# Power.net
KiCad netlist of a schematic drawn in Altium Designer
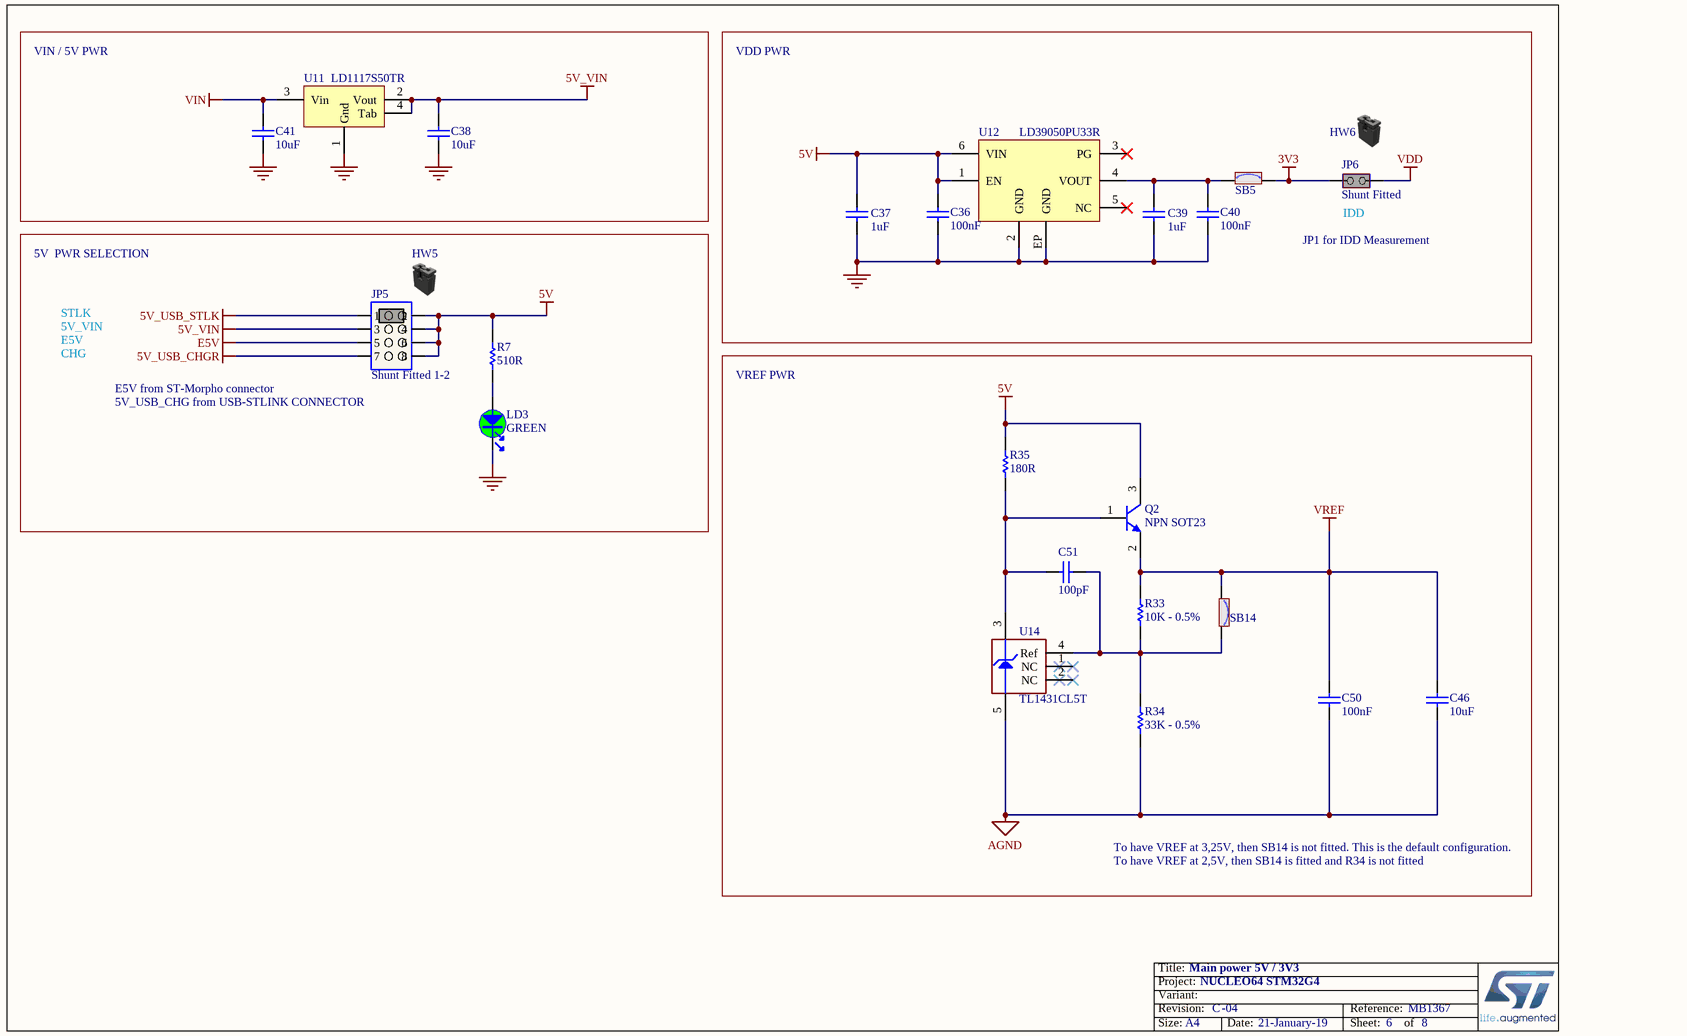
[diagram p0: Power.SchDoc]

(export (version "E")
  (design (tool "Eeschema 10.0.6"))
  (components
    (comp (ref "C36")
      (value "100nF")
      (footprint "C0402")
      (description "Capacitor, MLCC, 100nF, 16V, X7R, 10%, 0402, T=0,5mm")
      (fields
        (field (name "INTERNAL_PART_NUMBER") "MCD-00102")
        (field (name "MANUFACTURER_PART_NUMBER") "CC0402KRX7R7BB104")
        (field (name "PROVIDED_BY") "Subcon")
      )
      (libsource (lib "MCD_PARTS_database") (part "Capacitor"))
    )
    (comp (ref "C37")
      (value "1uF")
      (footprint "C0603")
      (description "Capacitor, MLCC, 1uF, 16V, X5R, 10%, 0603, T=0,8mm")
      (fields
        (field (name "INTERNAL_PART_NUMBER") "MCD-00010")
        (field (name "MANUFACTURER_PART_NUMBER") "CC0603KRX5R7BB105")
        (field (name "PROVIDED_BY") "Subcon")
      )
      (libsource (lib "MCD_PARTS_database") (part "Capacitor"))
    )
    (comp (ref "C38")
      (value "10uF")
      (footprint "C0805")
      (description "Capacitor, MLCC, 10uF, 25V, X5R, 10%, 0805, T=0,85mm")
      (fields
        (field (name "INTERNAL_PART_NUMBER") "MCD-00014")
        (field (name "MANUFACTURER_PART_NUMBER") "CC0805KRX5R8BB106")
        (field (name "PROVIDED_BY") "SUBCO")
      )
      (libsource (lib "MCD_PARTS_database") (part "Capacitor"))
    )
    (comp (ref "C39")
      (value "1uF")
      (footprint "C0603")
      (description "Capacitor, MLCC, 1uF, 16V, X5R, 10%, 0603, T=0,8mm")
      (fields
        (field (name "INTERNAL_PART_NUMBER") "MCD-00010")
        (field (name "MANUFACTURER_PART_NUMBER") "CC0603KRX5R7BB105")
        (field (name "PROVIDED_BY") "Subcon")
      )
      (libsource (lib "MCD_PARTS_database") (part "Capacitor"))
    )
    (comp (ref "C40")
      (value "100nF")
      (footprint "C0402")
      (description "Capacitor, MLCC, 100nF, 16V, X7R, 10%, 0402, T=0,5mm")
      (fields
        (field (name "INTERNAL_PART_NUMBER") "MCD-00102")
        (field (name "MANUFACTURER_PART_NUMBER") "CC0402KRX7R7BB104")
        (field (name "PROVIDED_BY") "Subcon")
      )
      (libsource (lib "MCD_PARTS_database") (part "Capacitor"))
    )
    (comp (ref "C41")
      (value "10uF")
      (footprint "C0805")
      (description "Capacitor, MLCC, 10uF, 25V, X5R, 10%, 0805, T=0,85mm")
      (fields
        (field (name "INTERNAL_PART_NUMBER") "MCD-00014")
        (field (name "MANUFACTURER_PART_NUMBER") "CC0805KRX5R8BB106")
        (field (name "PROVIDED_BY") "SUBCO")
      )
      (libsource (lib "MCD_PARTS_database") (part "Capacitor"))
    )
    (comp (ref "C46")
      (value "10uF")
      (footprint "C0603")
      (description "Capacitor, MLCC, 10uF, 10V, X5R, 10%, 0603, T=0.8mm")
      (fields
        (field (name "INTERNAL_PART_NUMBER") "MCD-01124")
        (field (name "MANUFACTURER_PART_NUMBER") "GRM188R61A106KAAL")
        (field (name "PROVIDED_BY") "SUBCO")
      )
      (libsource (lib "MCD_PARTS_database") (part "Capacitor"))
    )
    (comp (ref "C50")
      (value "100nF")
      (footprint "C0603")
      (description "Capacitor, MLCC, 100nF, 16V, X7R, 10%, 0603, T=0,8mm")
      (fields
        (field (name "INTERNAL_PART_NUMBER") "MCD-00211")
        (field (name "MANUFACTURER_PART_NUMBER") "CC0603KRX7R7BB104")
        (field (name "PROVIDED_BY") "SUBCO")
      )
      (libsource (lib "MCD_PARTS_database") (part "Capacitor"))
    )
    (comp (ref "C51")
      (value "100pF")
      (footprint "C0603")
      (description "Capacitor,100pF,50V,X7R,10%,0603")
      (fields
        (field (name "INTERNAL_PART_NUMBER") "MCD-01101")
        (field (name "MANUFACTURER_PART_NUMBER") "06035C101JAT4A")
        (field (name "PROVIDED_BY") "SUBCO")
      )
      (libsource (lib "MCD_PARTS_database") (part "Capacitor"))
    )
    (comp (ref "HW5")
      (value "~")
      (description "SHUNT 2.54mm BLACK")
      (fields
        (field (name "INTERNAL_PART_NUMBER") "MCD-00043")
        (field (name "MANUFACTURER_PART_NUMBER") "SNT-100-BK-G")
        (field (name "PROVIDED_BY") "Subcon")
      )
      (libsource (lib "MCD_PARTS_database") (part "Shunt Black 2.54mm"))
    )
    (comp (ref "HW6")
      (value "~")
      (description "SHUNT 2.54mm BLACK")
      (fields
        (field (name "INTERNAL_PART_NUMBER") "MCD-00043")
        (field (name "MANUFACTURER_PART_NUMBER") "SNT-100-BK-G")
        (field (name "PROVIDED_BY") "Subcon")
      )
      (libsource (lib "MCD_PARTS_database") (part "Shunt Black 2.54mm"))
    )
    (comp (ref "JP5")
      (value "Shunt Fitted 1-2")
      (footprint "CON_SAMTEC_TSW-104-07-X-D")
      (description "Header, 4x2, 2,54mm, VR, TH, Height 5.84mm/2.54mm - Shunt Fitted 1-2")
      (fields
        (field (name "INTERNAL_PART_NUMBER") "MCD-00686")
        (field (name "MANUFACTURER_PART_NUMBER") "TSW-104-07-x-D")
        (field (name "PROVIDED_BY") "SUBCO")
      )
      (libsource (lib "MCD_PARTS_database") (part "Jumper_Header 4x2 Fitted 1-2"))
    )
    (comp (ref "JP6")
      (value "Shunt Fitted")
      (footprint "CON_SAMTEC_TSW-102-07-G-S")
      (description "Header, 2x1, 2,54mm, VR, TH, Height 5.84mm/2.54mm - Shunt Fitted by default")
      (fields
        (field (name "INTERNAL_PART_NUMBER") "MCD-00683")
        (field (name "MANUFACTURER_PART_NUMBER") "TSW-102-07-x-S")
        (field (name "PROVIDED_BY") "Subcon")
      )
      (libsource (lib "MCD_PARTS_database") (part "Jumper_Header 2x1 Fitted"))
    )
    (comp (ref "LD3")
      (value "GREEN")
      (footprint "LED_0603_GREEN")
      (description "LED, Green, 0603")
      (fields
        (field (name "INTERNAL_PART_NUMBER") "MCD-00050")
        (field (name "MANUFACTURER_PART_NUMBER") "19-213SYGC/S530-E2/TR8")
        (field (name "PROVIDED_BY") "SUBCO")
      )
      (libsource (lib "MCD_PARTS_database") (part "LED_green"))
    )
    (comp (ref "Q2")
      (value "NPN SOT23")
      (footprint "NPN_SOT23")
      (description "NPN Bipolar Transistor")
      (fields
        (field (name "INTERNAL_PART_NUMBER") "MCD-00073")
        (field (name "MANUFACTURER_PART_NUMBER") "BSR14")
        (field (name "PROVIDED_BY") "SUBCO")
      )
      (libsource (lib "MCD_PARTS_database") (part "9013-SOT23"))
    )
    (comp (ref "R7")
      (value "510R")
      (footprint "R0603")
      (description "Resistor,510R,0603,1%,1/10W")
      (fields
        (field (name "INTERNAL_PART_NUMBER") "MCD-00225")
        (field (name "MANUFACTURER_PART_NUMBER") "RC0603FR-07510RL")
        (field (name "PROVIDED_BY") "SUBCO")
      )
      (libsource (lib "MCD_PARTS_database") (part "Resistor"))
    )
    (comp (ref "R33")
      (value "10K - 0.5%")
      (footprint "R0603")
      (description "resistor, 10K, 0603, 0.5%, 1/10W")
      (fields
        (field (name "INTERNAL_PART_NUMBER") "MCD-01215")
        (field (name "MANUFACTURER_PART_NUMBER") "RC0603DR-0710KL")
        (field (name "PROVIDED_BY") "SUBCO")
      )
      (libsource (lib "MCD_PARTS_database") (part "Resistor"))
    )
    (comp (ref "R34")
      (value "33K - 0.5%")
      (footprint "R0603")
      (description "Resistor,33K,0603,0.5%,1/10W")
      (fields
        (field (name "INTERNAL_PART_NUMBER") "MCD-01209")
        (field (name "MANUFACTURER_PART_NUMBER") "RC0603DR-0733KL")
        (field (name "PROVIDED_BY") "SUBCO")
      )
      (libsource (lib "MCD_PARTS_database") (part "Resistor"))
    )
    (comp (ref "R35")
      (value "180R")
      (footprint "R0603")
      (description "Resistor,180R,0603,1%,1/10W")
      (fields
        (field (name "INTERNAL_PART_NUMBER") "MCD-00342")
        (field (name "MANUFACTURER_PART_NUMBER") "RC0603FR-07180RL")
        (field (name "PROVIDED_BY") "SUBCO")
      )
      (libsource (lib "MCD_PARTS_database") (part "Resistor"))
    )
    (comp (ref "SB5")
      (value "~")
      (footprint "SOLDER-BRIDGE_R0603-0R")
      (description "Solder Bridge ON")
      (fields
        (field (name "INTERNAL_PART_NUMBER") "MCD-00071")
        (field (name "MANUFACTURER_PART_NUMBER") "RC0603JR-070RL")
        (field (name "PROVIDED_BY") "SUBCO")
      )
      (libsource (lib "") (part "SB_ON_1"))
    )
    (comp (ref "SB14")
      (value "~")
      (footprint "SOLDER-BRIDGE_R0603-0R")
      (description "Solder Bridge ON")
      (fields
        (field (name "INTERNAL_PART_NUMBER") "MCD-00071")
        (field (name "MANUFACTURER_PART_NUMBER") "RC0603JR-070RL")
        (field (name "PROVIDED_BY") "SUBCO")
      )
      (libsource (lib "MCD_PARTS_database") (part "SB_ON"))
    )
    (comp (ref "U11")
      (value "LD1117S50TR")
      (footprint "REG_SOT223-TAB")
      (description "IC REG LDO 5V 0.8A SOT223")
      (fields
        (field (name "INTERNAL_PART_NUMBER") "MCD-00088")
        (field (name "MANUFACTURER") "STMICROELECTRONICS")
        (field (name "PROVIDED_BY") "SUBCO with ST control")
      )
      (libsource (lib "MCD_PARTS_database") (part "LD1117S50TR"))
    )
    (comp (ref "U12")
      (value "LD39050PU33R")
      (footprint "ICC_DFN6-EPAD_3X3_P095")
      (description "Low quiescent current and low noise voltage regulators")
      (fields
        (field (name "INTERNAL_PART_NUMBER") "MCD-00215")
        (field (name "MANUFACTURER") "STMICROELECTRONICS")
        (field (name "PROVIDED_BY") "SUBCO with ST control")
      )
      (libsource (lib "MCD_PARTS_database") (part "LD39050PU33R"))
    )
    (comp (ref "U14")
      (value "TL1431CL5T")
      (footprint "ICC_SOT23-5L_H1P45")
      (description "Programmable voltage reference with 0.4% voltage precision")
      (fields
        (field (name "INTERNAL_PART_NUMBER") "MCD-01802")
        (field (name "MANUFACTURER") "STMICROELECTRONICS")
        (field (name "PROVIDED_BY") "SUBCO with ST control")
      )
      (libsource (lib "MCD_PARTS_database") (part "TL1431ACL5T"))
    )
  )
  (nets
    (net (code "1") (name "3V3") (class "Default")
      (node (ref "JP6") (pin "1") (pinfunction "COMMON_1") (pintype "passive"))
      (node (ref "SB5") (pin "2") (pinfunction "2_2") (pintype "passive"))
    )
    (net (code "2") (name "5V") (class "Default")
      (node (ref "C36") (pin "2") (pinfunction "2_2") (pintype "passive"))
      (node (ref "C37") (pin "2") (pinfunction "2_2") (pintype "passive"))
      (node (ref "JP5") (pin "2") (pinfunction "2_2") (pintype "passive"))
      (node (ref "JP5") (pin "4") (pinfunction "4_4") (pintype "passive"))
      (node (ref "JP5") (pin "6") (pinfunction "6_6") (pintype "passive"))
      (node (ref "JP5") (pin "8") (pinfunction "8_8") (pintype "passive"))
      (node (ref "Q2") (pin "3") (pinfunction "C_3") (pintype "passive"))
      (node (ref "R35") (pin "2") (pinfunction "2_2") (pintype "passive"))
      (node (ref "R7") (pin "2") (pinfunction "2_2") (pintype "passive"))
      (node (ref "U12") (pin "1") (pinfunction "EN_1") (pintype "passive"))
      (node (ref "U12") (pin "6") (pinfunction "VIN_6") (pintype "passive"))
    )
    (net (code "3") (name "5V_USB_CHGR") (class "Default")
      (node (ref "JP5") (pin "7") (pinfunction "7_7") (pintype "passive"))
    )
    (net (code "4") (name "5V_USB_STLK") (class "Default")
      (node (ref "JP5") (pin "1") (pinfunction "1_1") (pintype "passive"))
    )
    (net (code "5") (name "5V_VIN") (class "Default")
      (node (ref "C38") (pin "2") (pinfunction "2_2") (pintype "passive"))
      (node (ref "JP5") (pin "3") (pinfunction "3_3") (pintype "passive"))
      (node (ref "U11") (pin "2") (pinfunction "Vout_2") (pintype "passive"))
      (node (ref "U11") (pin "4") (pinfunction "Tab_4") (pintype "passive"))
    )
    (net (code "6") (name "AGND") (class "Default")
      (node (ref "C46") (pin "1") (pinfunction "1_1") (pintype "passive"))
      (node (ref "C50") (pin "1") (pinfunction "1_1") (pintype "passive"))
      (node (ref "R34") (pin "1") (pinfunction "1_1") (pintype "passive"))
      (node (ref "U14") (pin "5") (pinfunction "Anode_5") (pintype "passive"))
    )
    (net (code "7") (name "E5V") (class "Default")
      (node (ref "JP5") (pin "5") (pinfunction "5_5") (pintype "passive"))
    )
    (net (code "8") (name "GND") (class "Default")
      (node (ref "C36") (pin "1") (pinfunction "1_1") (pintype "passive"))
      (node (ref "C37") (pin "1") (pinfunction "1_1") (pintype "passive"))
      (node (ref "C38") (pin "1") (pinfunction "1_1") (pintype "passive"))
      (node (ref "C39") (pin "1") (pinfunction "1_1") (pintype "passive"))
      (node (ref "C40") (pin "1") (pinfunction "1_1") (pintype "passive"))
      (node (ref "C41") (pin "1") (pinfunction "1_1") (pintype "passive"))
      (node (ref "LD3") (pin "2") (pintype "passive"))
      (node (ref "U11") (pin "1") (pinfunction "Gnd_1") (pintype "passive"))
      (node (ref "U12") (pin "2") (pinfunction "GND_2") (pintype "passive"))
      (node (ref "U12") (pin "EP") (pinfunction "GND_EP") (pintype "passive"))
    )
    (net (code "9") (name "Net-(LD3-Pad1)") (class "Default")
      (node (ref "LD3") (pin "1") (pintype "passive"))
      (node (ref "R7") (pin "1") (pinfunction "1_1") (pintype "passive"))
    )
    (net (code "10") (name "Net-(Q2-B)") (class "Default")
      (node (ref "C51") (pin "1") (pinfunction "1_1") (pintype "passive"))
      (node (ref "Q2") (pin "1") (pinfunction "B_1") (pintype "passive"))
      (node (ref "R35") (pin "1") (pinfunction "1_1") (pintype "passive"))
      (node (ref "U14") (pin "3") (pinfunction "Cathode_3") (pintype "passive"))
    )
    (net (code "11") (name "Net-(U12-VOUT)") (class "Default")
      (node (ref "C39") (pin "2") (pinfunction "2_2") (pintype "passive"))
      (node (ref "C40") (pin "2") (pinfunction "2_2") (pintype "passive"))
      (node (ref "SB5") (pin "1") (pinfunction "1_1") (pintype "passive"))
      (node (ref "U12") (pin "4") (pinfunction "VOUT_4") (pintype "passive"))
    )
    (net (code "12") (name "Net-(U14-Ref)") (class "Default")
      (node (ref "C51") (pin "2") (pinfunction "2_2") (pintype "passive"))
      (node (ref "R33") (pin "1") (pinfunction "1_1") (pintype "passive"))
      (node (ref "R34") (pin "2") (pinfunction "2_2") (pintype "passive"))
      (node (ref "SB14") (pin "2") (pinfunction "2_2") (pintype "passive"))
      (node (ref "U14") (pin "4") (pinfunction "Ref_4") (pintype "passive"))
    )
    (net (code "13") (name "VDD") (class "Default")
      (node (ref "JP6") (pin "2") (pinfunction "NO_2") (pintype "passive"))
    )
    (net (code "14") (name "VIN") (class "Default")
      (node (ref "C41") (pin "2") (pinfunction "2_2") (pintype "passive"))
      (node (ref "U11") (pin "3") (pinfunction "Vin_3") (pintype "passive"))
    )
    (net (code "15") (name "VREF") (class "Default")
      (node (ref "C46") (pin "2") (pinfunction "2_2") (pintype "passive"))
      (node (ref "C50") (pin "2") (pinfunction "2_2") (pintype "passive"))
      (node (ref "Q2") (pin "2") (pinfunction "E_2") (pintype "passive"))
      (node (ref "R33") (pin "2") (pinfunction "2_2") (pintype "passive"))
      (node (ref "SB14") (pin "1") (pinfunction "1_1") (pintype "passive"))
    )
    (net (code "16") (name "unconnected-(U12-NC-Pad5)") (class "Default")
      (node (ref "U12") (pin "5") (pinfunction "NC_5") (pintype "passive+no_connect"))
    )
    (net (code "17") (name "unconnected-(U12-PG-Pad3)") (class "Default")
      (node (ref "U12") (pin "3") (pinfunction "PG_3") (pintype "passive+no_connect"))
    )
    (net (code "18") (name "unconnected-(U14-NC-Pad1)") (class "Default")
      (node (ref "U14") (pin "1") (pinfunction "NC_1") (pintype "passive+no_connect"))
    )
    (net (code "19") (name "unconnected-(U14-NC-Pad2)") (class "Default")
      (node (ref "U14") (pin "2") (pinfunction "NC_2") (pintype "passive+no_connect"))
    )
  )
)
